# ProPrj___2025-04-18.net
KiCad netlist of a schematic drawn in EasyEDA Pro
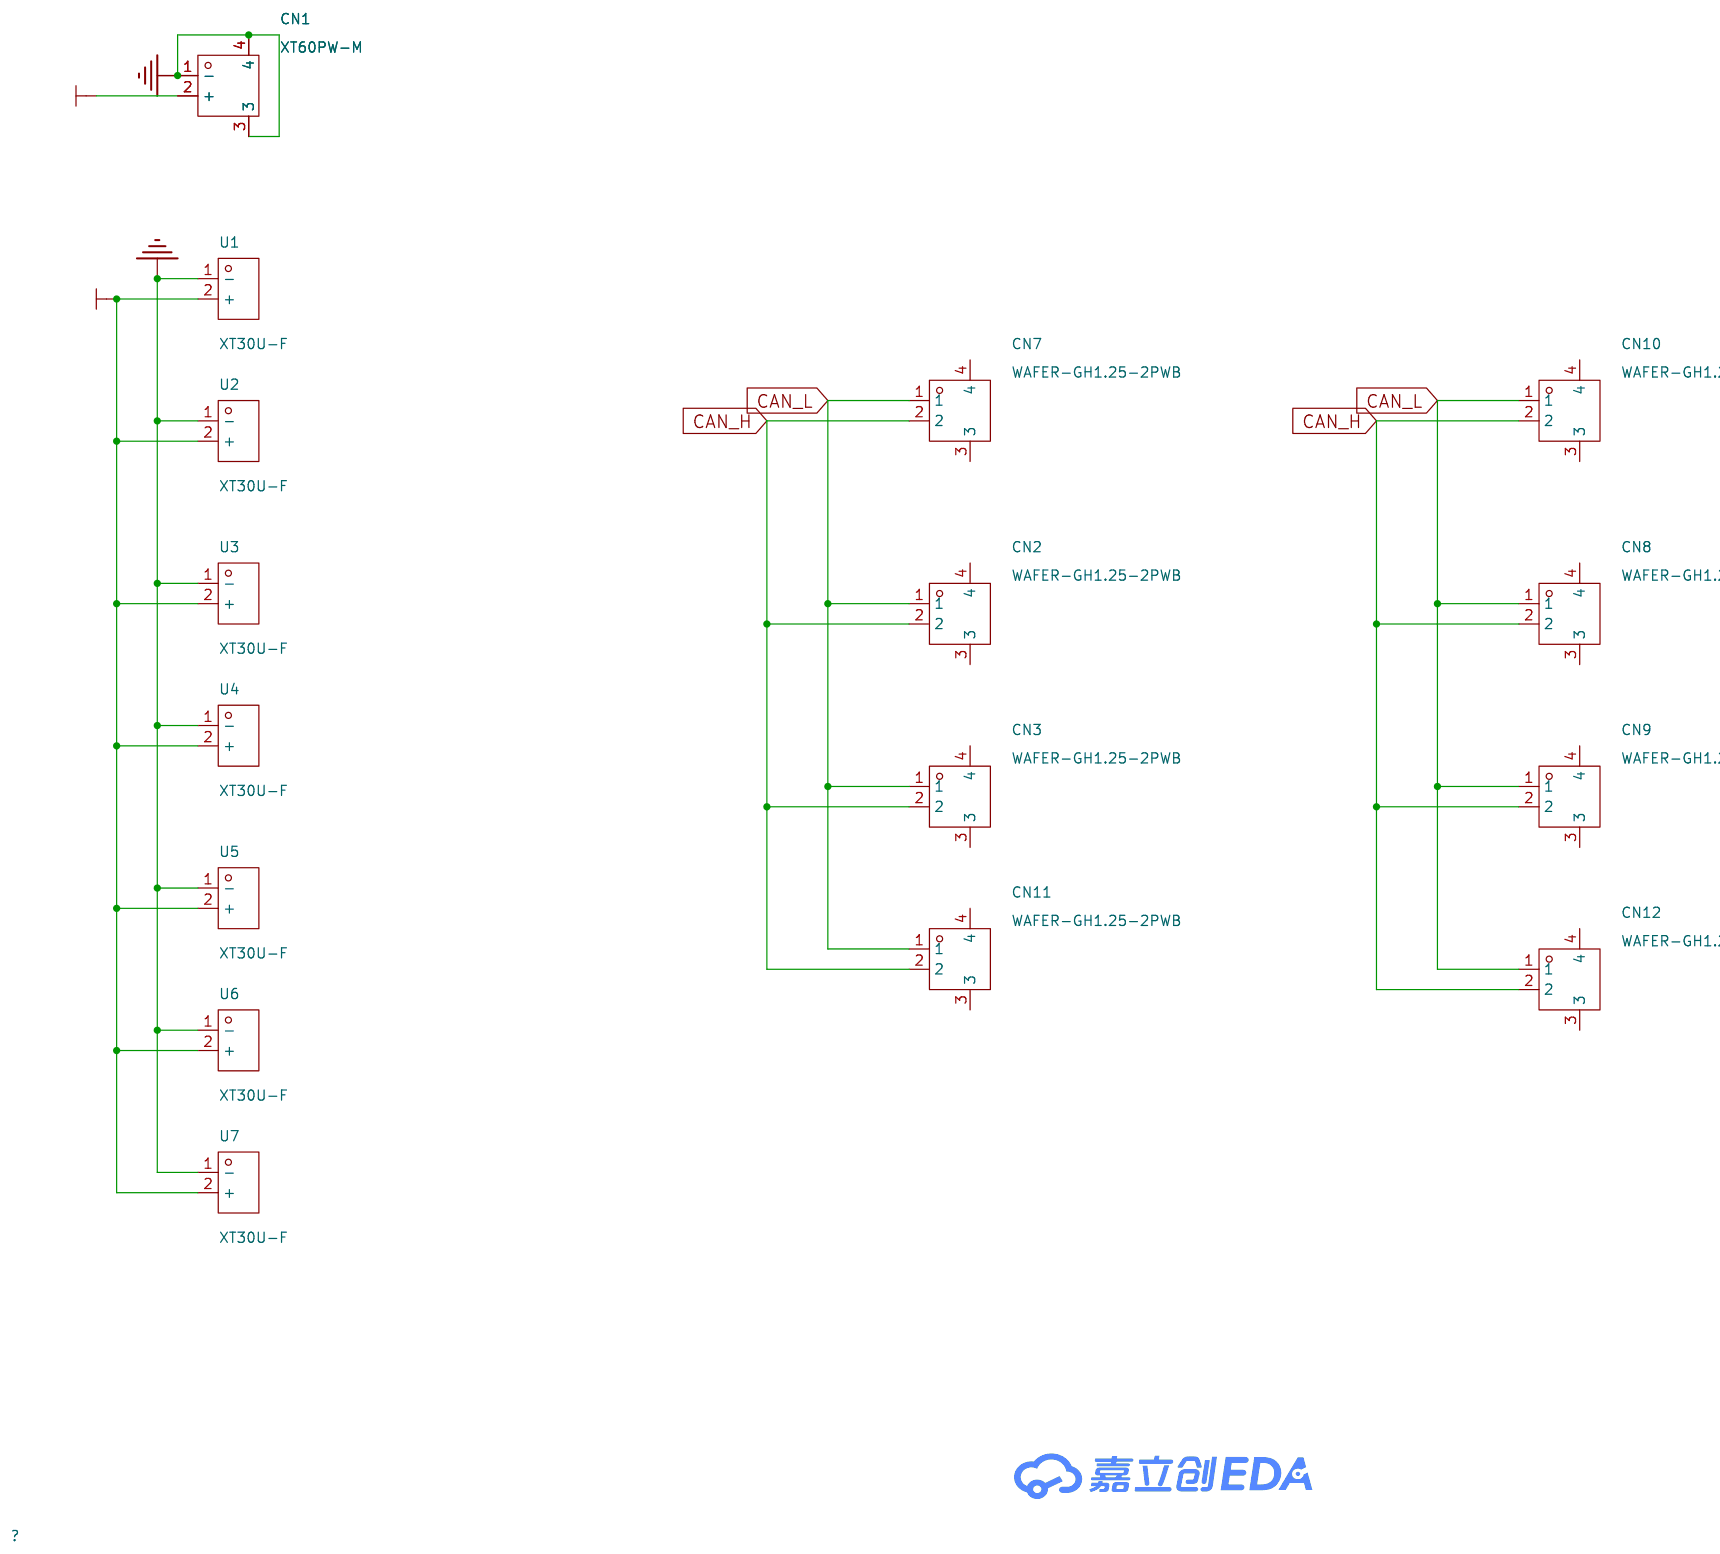
[diagram p0: schematic sheet]

(export (version "E")
  (design (tool "Eeschema 10.0.6"))
  (components
    (comp (ref "CN1")
      (value "XT60PW-M")
      (footprint "easyedapro:CONN-TH_XT60PW-M")
      (description "类别:-;类型1:-;")
      (fields (field (name "Manufacturer") "AMASS(艾迈斯)"))
      (libsource (lib "easyedapro") (part "XT60PW-M"))
    )
    (comp (ref "CN2")
      (value "WAFER-GH1.25-2PWB")
      (footprint "easyedapro:CONN-TH_2P-P1.25_XUNPU_WAFER-GH1.25-2PWB")
      (fields (field (name "Manufacturer") "XUNPU(讯普)"))
      (libsource (lib "easyedapro") (part "WAFER-GH1.25-2PWB"))
    )
    (comp (ref "CN3")
      (value "WAFER-GH1.25-2PWB")
      (footprint "easyedapro:CONN-TH_2P-P1.25_XUNPU_WAFER-GH1.25-2PWB")
      (fields (field (name "Manufacturer") "XUNPU(讯普)"))
      (libsource (lib "easyedapro") (part "WAFER-GH1.25-2PWB"))
    )
    (comp (ref "CN7")
      (value "WAFER-GH1.25-2PWB")
      (footprint "easyedapro:CONN-TH_2P-P1.25_XUNPU_WAFER-GH1.25-2PWB")
      (fields (field (name "Manufacturer") "XUNPU(讯普)"))
      (libsource (lib "easyedapro") (part "WAFER-GH1.25-2PWB"))
    )
    (comp (ref "CN8")
      (value "WAFER-GH1.25-2PWB")
      (footprint "easyedapro:CONN-TH_2P-P1.25_XUNPU_WAFER-GH1.25-2PWB")
      (fields (field (name "Manufacturer") "XUNPU(讯普)"))
      (libsource (lib "easyedapro") (part "WAFER-GH1.25-2PWB"))
    )
    (comp (ref "CN9")
      (value "WAFER-GH1.25-2PWB")
      (footprint "easyedapro:CONN-TH_2P-P1.25_XUNPU_WAFER-GH1.25-2PWB")
      (fields (field (name "Manufacturer") "XUNPU(讯普)"))
      (libsource (lib "easyedapro") (part "WAFER-GH1.25-2PWB"))
    )
    (comp (ref "CN10")
      (value "WAFER-GH1.25-2PWB")
      (footprint "easyedapro:CONN-TH_2P-P1.25_XUNPU_WAFER-GH1.25-2PWB")
      (fields (field (name "Manufacturer") "XUNPU(讯普)"))
      (libsource (lib "easyedapro") (part "WAFER-GH1.25-2PWB"))
    )
    (comp (ref "CN11")
      (value "WAFER-GH1.25-2PWB")
      (footprint "easyedapro:CONN-TH_2P-P1.25_XUNPU_WAFER-GH1.25-2PWB")
      (fields (field (name "Manufacturer") "XUNPU(讯普)"))
      (libsource (lib "easyedapro") (part "WAFER-GH1.25-2PWB"))
    )
    (comp (ref "CN12")
      (value "WAFER-GH1.25-2PWB")
      (footprint "easyedapro:CONN-TH_2P-P1.25_XUNPU_WAFER-GH1.25-2PWB")
      (fields (field (name "Manufacturer") "XUNPU(讯普)"))
      (libsource (lib "easyedapro") (part "WAFER-GH1.25-2PWB"))
    )
    (comp (ref "U1")
      (value "XT30U-F")
      (footprint "easyedapro:CONN-TH_XT30U-F")
      (description "类别:-;类型1:-;")
      (fields (field (name "Manufacturer") "AMASS(艾迈斯)"))
      (libsource (lib "easyedapro") (part "XT30U-F"))
    )
    (comp (ref "U2")
      (value "XT30U-F")
      (footprint "easyedapro:CONN-TH_XT30U-F")
      (description "类别:-;类型1:-;")
      (fields (field (name "Manufacturer") "AMASS(艾迈斯)"))
      (libsource (lib "easyedapro") (part "XT30U-F"))
    )
    (comp (ref "U3")
      (value "XT30U-F")
      (footprint "easyedapro:CONN-TH_XT30U-F")
      (description "类别:-;类型1:-;")
      (fields (field (name "Manufacturer") "AMASS(艾迈斯)"))
      (libsource (lib "easyedapro") (part "XT30U-F"))
    )
    (comp (ref "U4")
      (value "XT30U-F")
      (footprint "easyedapro:CONN-TH_XT30U-F")
      (description "类别:-;类型1:-;")
      (fields (field (name "Manufacturer") "AMASS(艾迈斯)"))
      (libsource (lib "easyedapro") (part "XT30U-F"))
    )
    (comp (ref "U5")
      (value "XT30U-F")
      (footprint "easyedapro:CONN-TH_XT30U-F")
      (description "类别:-;类型1:-;")
      (fields (field (name "Manufacturer") "AMASS(艾迈斯)"))
      (libsource (lib "easyedapro") (part "XT30U-F"))
    )
    (comp (ref "U6")
      (value "XT30U-F")
      (footprint "easyedapro:CONN-TH_XT30U-F")
      (description "类别:-;类型1:-;")
      (fields (field (name "Manufacturer") "AMASS(艾迈斯)"))
      (libsource (lib "easyedapro") (part "XT30U-F"))
    )
    (comp (ref "U7")
      (value "XT30U-F")
      (footprint "easyedapro:CONN-TH_XT30U-F")
      (description "类别:-;类型1:-;")
      (fields (field (name "Manufacturer") "AMASS(艾迈斯)"))
      (libsource (lib "easyedapro") (part "XT30U-F"))
    )
  )
  (nets
    (net (code "1") (name "CAN_H") (class "Default")
      (node (ref "CN10") (pin "2") (pinfunction "2_2") (pintype "unspecified"))
      (node (ref "CN11") (pin "2") (pinfunction "2_2") (pintype "unspecified"))
      (node (ref "CN12") (pin "2") (pinfunction "2_2") (pintype "unspecified"))
      (node (ref "CN2") (pin "2") (pinfunction "2_2") (pintype "unspecified"))
      (node (ref "CN3") (pin "2") (pinfunction "2_2") (pintype "unspecified"))
      (node (ref "CN7") (pin "2") (pinfunction "2_2") (pintype "unspecified"))
      (node (ref "CN8") (pin "2") (pinfunction "2_2") (pintype "unspecified"))
      (node (ref "CN9") (pin "2") (pinfunction "2_2") (pintype "unspecified"))
    )
    (net (code "2") (name "CAN_L") (class "Default")
      (node (ref "CN10") (pin "1") (pinfunction "1_1") (pintype "unspecified"))
      (node (ref "CN11") (pin "1") (pinfunction "1_1") (pintype "unspecified"))
      (node (ref "CN12") (pin "1") (pinfunction "1_1") (pintype "unspecified"))
      (node (ref "CN2") (pin "1") (pinfunction "1_1") (pintype "unspecified"))
      (node (ref "CN3") (pin "1") (pinfunction "1_1") (pintype "unspecified"))
      (node (ref "CN7") (pin "1") (pinfunction "1_1") (pintype "unspecified"))
      (node (ref "CN8") (pin "1") (pinfunction "1_1") (pintype "unspecified"))
      (node (ref "CN9") (pin "1") (pinfunction "1_1") (pintype "unspecified"))
    )
    (net (code "3") (name "GND") (class "Default")
      (node (ref "CN1") (pin "1") (pinfunction "-_1") (pintype "unspecified"))
      (node (ref "CN1") (pin "3") (pinfunction "3_3") (pintype "unspecified"))
      (node (ref "CN1") (pin "4") (pinfunction "4_4") (pintype "unspecified"))
      (node (ref "U1") (pin "1") (pinfunction "-_1") (pintype "unspecified"))
      (node (ref "U2") (pin "1") (pinfunction "-_1") (pintype "unspecified"))
      (node (ref "U3") (pin "1") (pinfunction "-_1") (pintype "unspecified"))
      (node (ref "U4") (pin "1") (pinfunction "-_1") (pintype "unspecified"))
      (node (ref "U5") (pin "1") (pinfunction "-_1") (pintype "unspecified"))
      (node (ref "U6") (pin "1") (pinfunction "-_1") (pintype "unspecified"))
      (node (ref "U7") (pin "1") (pinfunction "-_1") (pintype "unspecified"))
    )
    (net (code "4") (name "VCC24V") (class "Default")
      (node (ref "CN1") (pin "2") (pinfunction "+_2") (pintype "unspecified"))
      (node (ref "U1") (pin "2") (pinfunction "+_2") (pintype "unspecified"))
      (node (ref "U2") (pin "2") (pinfunction "+_2") (pintype "unspecified"))
      (node (ref "U3") (pin "2") (pinfunction "+_2") (pintype "unspecified"))
      (node (ref "U4") (pin "2") (pinfunction "+_2") (pintype "unspecified"))
      (node (ref "U5") (pin "2") (pinfunction "+_2") (pintype "unspecified"))
      (node (ref "U6") (pin "2") (pinfunction "+_2") (pintype "unspecified"))
      (node (ref "U7") (pin "2") (pinfunction "+_2") (pintype "unspecified"))
    )
    (net (code "5") (name "unconnected-(CN2-Pad3)") (class "Default")
      (node (ref "CN2") (pin "3") (pinfunction "3_3") (pintype "unspecified"))
    )
    (net (code "6") (name "unconnected-(CN2-Pad4)") (class "Default")
      (node (ref "CN2") (pin "4") (pinfunction "4_4") (pintype "unspecified"))
    )
    (net (code "7") (name "unconnected-(CN3-Pad3)") (class "Default")
      (node (ref "CN3") (pin "3") (pinfunction "3_3") (pintype "unspecified"))
    )
    (net (code "8") (name "unconnected-(CN3-Pad4)") (class "Default")
      (node (ref "CN3") (pin "4") (pinfunction "4_4") (pintype "unspecified"))
    )
    (net (code "9") (name "unconnected-(CN7-Pad3)") (class "Default")
      (node (ref "CN7") (pin "3") (pinfunction "3_3") (pintype "unspecified"))
    )
    (net (code "10") (name "unconnected-(CN7-Pad4)") (class "Default")
      (node (ref "CN7") (pin "4") (pinfunction "4_4") (pintype "unspecified"))
    )
    (net (code "11") (name "unconnected-(CN8-Pad3)") (class "Default")
      (node (ref "CN8") (pin "3") (pinfunction "3_3") (pintype "unspecified"))
    )
    (net (code "12") (name "unconnected-(CN8-Pad4)") (class "Default")
      (node (ref "CN8") (pin "4") (pinfunction "4_4") (pintype "unspecified"))
    )
    (net (code "13") (name "unconnected-(CN9-Pad3)") (class "Default")
      (node (ref "CN9") (pin "3") (pinfunction "3_3") (pintype "unspecified"))
    )
    (net (code "14") (name "unconnected-(CN9-Pad4)") (class "Default")
      (node (ref "CN9") (pin "4") (pinfunction "4_4") (pintype "unspecified"))
    )
    (net (code "15") (name "unconnected-(CN10-Pad3)") (class "Default")
      (node (ref "CN10") (pin "3") (pinfunction "3_3") (pintype "unspecified"))
    )
    (net (code "16") (name "unconnected-(CN10-Pad4)") (class "Default")
      (node (ref "CN10") (pin "4") (pinfunction "4_4") (pintype "unspecified"))
    )
    (net (code "17") (name "unconnected-(CN11-Pad3)") (class "Default")
      (node (ref "CN11") (pin "3") (pinfunction "3_3") (pintype "unspecified"))
    )
    (net (code "18") (name "unconnected-(CN11-Pad4)") (class "Default")
      (node (ref "CN11") (pin "4") (pinfunction "4_4") (pintype "unspecified"))
    )
    (net (code "19") (name "unconnected-(CN12-Pad3)") (class "Default")
      (node (ref "CN12") (pin "3") (pinfunction "3_3") (pintype "unspecified"))
    )
    (net (code "20") (name "unconnected-(CN12-Pad4)") (class "Default")
      (node (ref "CN12") (pin "4") (pinfunction "4_4") (pintype "unspecified"))
    )
  )
)
